# Arduino_extension_connectors.net
KiCad netlist of a schematic drawn in Altium Designer
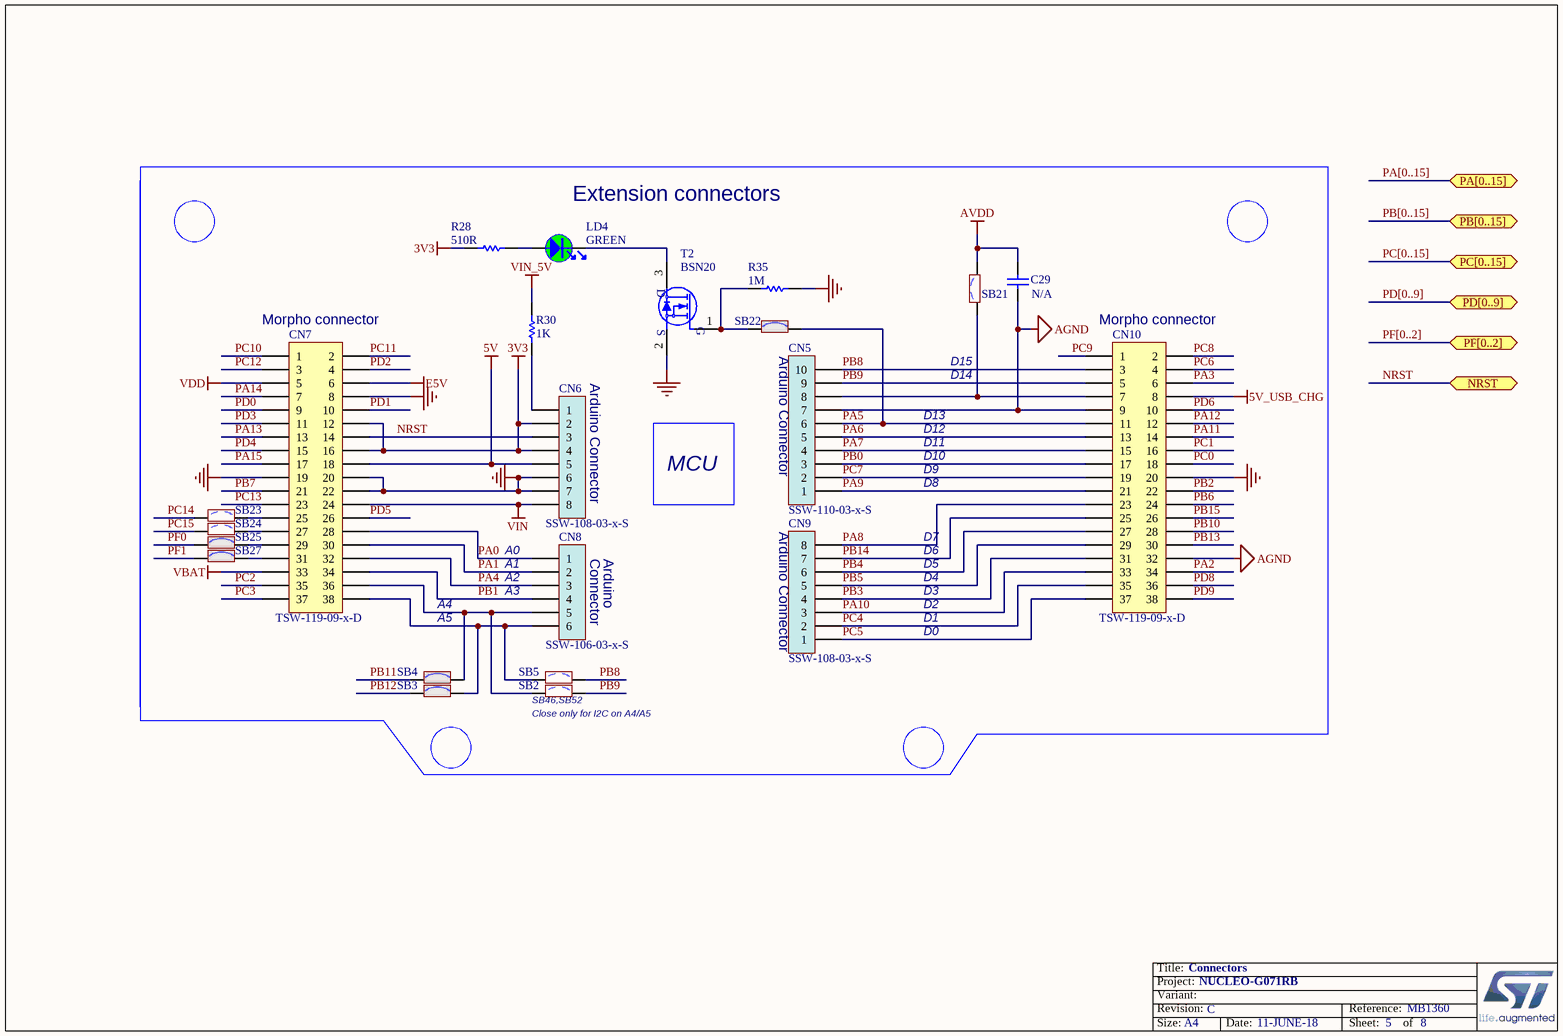
[diagram p0: Arduino_extension_connectors.SchDoc]

(export (version "E")
  (design (tool "Eeschema 10.0.6"))
  (components
    (comp (ref "C29")
      (value "N/A")
      (footprint "C0603")
      (description "Capacitor, MLCC, 100nF, 16V, X7R, 10%, 0603, T=0,8mm")
      (fields
        (field (name "INTERNAL_PART_NUMBER") "MCD-00211")
        (field (name "MANUFACTURER_PART_NUMBER") "CC0603KRX7R7BB104")
        (field (name "PROVIDED_BY") "Subcon")
      )
      (libsource (lib "MCD_PARTS_database") (part "Capacitor"))
    )
    (comp (ref "CN5")
      (value "Socket 10x1")
      (footprint "CON_SAMTEC_SSW-110-03-X-S")
      (description "Socket, 10x1, 2.54mm, VR, TH, Height 8.51mm/10mm")
      (fields
        (field (name "INTERNAL_PART_NUMBER") "MCD-00262")
        (field (name "MANUFACTURER_PART_NUMBER") "SSW-110-03-x-S")
        (field (name "MANUFACTURER") "SAMTEC")
        (field (name "PROVIDED_BY") "Subcon")
      )
      (libsource (lib "MCD_PARTS_database") (part "Socket 10x1"))
    )
    (comp (ref "CN6")
      (value "Socket 8x1")
      (footprint "CON_SAMTEC_SSW-108-03-X-S")
      (description "Socket, 8x1, 2.54mm, VR, TH, Height 8.51mm/10mm")
      (fields
        (field (name "INTERNAL_PART_NUMBER") "MCD-00261")
        (field (name "MANUFACTURER_PART_NUMBER") "SSW-108-03-x-S")
        (field (name "MANUFACTURER") "SAMTEC")
        (field (name "PROVIDED_BY") "Subcon")
      )
      (libsource (lib "") (part "Socket 8x1_1"))
    )
    (comp (ref "CN7")
      (value "Header 19x2")
      (footprint "CON_SAMTEC_TSW-119-09-X-D")
      (description "Header, 19x2, 2,54mm, VR, TH, Height 5.84mm/10.16mm")
      (fields
        (field (name "INTERNAL_PART_NUMBER") "MCD-00213")
        (field (name "MANUFACTURER_PART_NUMBER") "TSW-119-09-x-D")
        (field (name "MANUFACTURER") "SAMTEC")
        (field (name "PROVIDED_BY") "Subcon")
      )
      (libsource (lib "MCD_PARTS_database") (part "Header 19x2"))
    )
    (comp (ref "CN8")
      (value "Socket 6x1")
      (footprint "CON_SAMTEC_SSW-106-03-X-S")
      (description "Socket, 6x1, 2.54mm, VR, TH, Height 8.51mm/10mm")
      (fields
        (field (name "INTERNAL_PART_NUMBER") "MCD-00260")
        (field (name "MANUFACTURER_PART_NUMBER") "SSW-106-03-x-S")
        (field (name "MANUFACTURER") "SAMTEC")
        (field (name "PROVIDED_BY") "Subcon")
      )
      (libsource (lib "MCD_PARTS_database") (part "Socket 6x1"))
    )
    (comp (ref "CN9")
      (value "Socket 8x1")
      (footprint "CON_SAMTEC_SSW-108-03-X-S")
      (description "Socket, 8x1, 2.54mm, VR, TH, Height 8.51mm/10mm")
      (fields
        (field (name "INTERNAL_PART_NUMBER") "MCD-00261")
        (field (name "MANUFACTURER_PART_NUMBER") "SSW-108-03-x-S")
        (field (name "MANUFACTURER") "SAMTEC")
        (field (name "PROVIDED_BY") "Subcon")
      )
      (libsource (lib "MCD_PARTS_database") (part "Socket 8x1"))
    )
    (comp (ref "CN10")
      (value "Header 19x2")
      (footprint "CON_SAMTEC_TSW-119-09-X-D")
      (description "Header, 19x2, 2,54mm, VR, TH, Height 5.84mm/10.16mm")
      (fields
        (field (name "INTERNAL_PART_NUMBER") "MCD-00213")
        (field (name "MANUFACTURER_PART_NUMBER") "TSW-119-09-x-D")
        (field (name "MANUFACTURER") "SAMTEC")
        (field (name "PROVIDED_BY") "Subcon")
      )
      (libsource (lib "MCD_PARTS_database") (part "Header 19x2"))
    )
    (comp (ref "LD4")
      (value "GREEN")
      (footprint "LED_0603_GREEN")
      (description "LED, Green, 0603")
      (fields
        (field (name "INTERNAL_PART_NUMBER") "MCD-00050")
        (field (name "MANUFACTURER_PART_NUMBER") "19-213SYGC/S530-E2/TR8")
        (field (name "PROVIDED_BY") "Subcon")
      )
      (libsource (lib "MCD_PARTS_database") (part "LED_green"))
    )
    (comp (ref "R28")
      (value "510R")
      (footprint "R0603")
      (description "Resistor,510R,0603,1%,1/10W")
      (fields
        (field (name "INTERNAL_PART_NUMBER") "MCD-00225")
        (field (name "MANUFACTURER_PART_NUMBER") "RC0603FR-07510RL")
        (field (name "PROVIDED_BY") "Subcon")
      )
      (libsource (lib "MCD_PARTS_database") (part "Resistor"))
    )
    (comp (ref "R30")
      (value "1K")
      (footprint "R0603")
      (description "Resistor,1K,0603,1%,1/10W")
      (fields
        (field (name "INTERNAL_PART_NUMBER") "MCD-00070")
        (field (name "MANUFACTURER_PART_NUMBER") "RC0603FR-071KL")
        (field (name "PROVIDED_BY") "Subcon")
      )
      (libsource (lib "MCD_PARTS_database") (part "Resistor"))
    )
    (comp (ref "R35")
      (value "1M")
      (footprint "R0603")
      (description "Resistor,1M,0603,1%,1/10W")
      (fields
        (field (name "INTERNAL_PART_NUMBER") "MCD-00257")
        (field (name "MANUFACTURER_PART_NUMBER") "RC0603FR-071ML")
        (field (name "PROVIDED_BY") "Subcon")
      )
      (libsource (lib "MCD_PARTS_database") (part "Resistor"))
    )
    (comp (ref "SB2")
      (value "SB_OFF")
      (footprint "SOLDER-BRIDGE_R0603-0R")
      (description "Solder Bridge OFF")
      (fields (field (name "INTERNAL_PART_NUMBER") "MCD-00072"))
      (libsource (lib "MCD_PARTS_database") (part "SB_OFF"))
    )
    (comp (ref "SB3")
      (value "SB_ON")
      (footprint "SOLDER-BRIDGE_R0603-0R")
      (description "Solder Bridge ON")
      (fields (field (name "INTERNAL_PART_NUMBER") "MCD-00071") (field (name "PROVIDED_BY") "Subcon"))
      (libsource (lib "MCD_PARTS_database") (part "SB_ON"))
    )
    (comp (ref "SB4")
      (value "SB_ON")
      (footprint "SOLDER-BRIDGE_R0603-0R")
      (description "Solder Bridge ON")
      (fields (field (name "INTERNAL_PART_NUMBER") "MCD-00071") (field (name "PROVIDED_BY") "Subcon"))
      (libsource (lib "MCD_PARTS_database") (part "SB_ON"))
    )
    (comp (ref "SB5")
      (value "SB_OFF")
      (footprint "SOLDER-BRIDGE_R0603-0R")
      (description "Solder Bridge OFF")
      (fields (field (name "INTERNAL_PART_NUMBER") "MCD-00072"))
      (libsource (lib "MCD_PARTS_database") (part "SB_OFF"))
    )
    (comp (ref "SB21")
      (value "SB_OFF")
      (footprint "SOLDER-BRIDGE_R0603-0R")
      (description "Solder Bridge OFF")
      (fields (field (name "INTERNAL_PART_NUMBER") "MCD-00072"))
      (libsource (lib "") (part "SB_OFF_1"))
    )
    (comp (ref "SB22")
      (value "SB_ON")
      (footprint "SOLDER-BRIDGE_R0603-0R")
      (description "Solder Bridge ON")
      (fields (field (name "INTERNAL_PART_NUMBER") "MCD-00071") (field (name "PROVIDED_BY") "Subcon"))
      (libsource (lib "MCD_PARTS_database") (part "SB_ON"))
    )
    (comp (ref "SB23")
      (value "SB_OFF")
      (footprint "SOLDER-BRIDGE_R0603-0R")
      (description "Solder Bridge OFF")
      (fields (field (name "INTERNAL_PART_NUMBER") "MCD-00072"))
      (libsource (lib "MCD_PARTS_database") (part "SB_OFF"))
    )
    (comp (ref "SB24")
      (value "SB_OFF")
      (footprint "SOLDER-BRIDGE_R0603-0R")
      (description "Solder Bridge OFF")
      (fields (field (name "INTERNAL_PART_NUMBER") "MCD-00072"))
      (libsource (lib "MCD_PARTS_database") (part "SB_OFF"))
    )
    (comp (ref "SB25")
      (value "SB_ON")
      (footprint "SOLDER-BRIDGE_R0603-0R")
      (description "Solder Bridge ON")
      (fields (field (name "INTERNAL_PART_NUMBER") "MCD-00071") (field (name "PROVIDED_BY") "Subcon"))
      (libsource (lib "MCD_PARTS_database") (part "SB_ON"))
    )
    (comp (ref "SB27")
      (value "SB_ON")
      (footprint "SOLDER-BRIDGE_R0603-0R")
      (description "Solder Bridge ON")
      (fields (field (name "INTERNAL_PART_NUMBER") "MCD-00071") (field (name "PROVIDED_BY") "Subcon"))
      (libsource (lib "MCD_PARTS_database") (part "SB_ON"))
    )
    (comp (ref "T2")
      (value "BSN20")
      (footprint "MOS_SOT23")
      (description "N-channel enhancement mode field-effect transistor")
      (fields
        (field (name "INTERNAL_PART_NUMBER") "MCD-00151")
        (field (name "MANUFACTURER") "NXP")
        (field (name "PROVIDED_BY") "Subcon")
      )
      (libsource (lib "MCD_PARTS_database") (part "BSN20"))
    )
  )
  (nets
    (net (code "3") (name "/NRST") (class "Default")
      (node (ref "CN6") (pin "3") (pinfunction "3_3") (pintype "passive"))
      (node (ref "CN7") (pin "14") (pinfunction "14_14") (pintype "passive"))
    )
    (net (code "4") (name "/PA0") (class "Default")
      (node (ref "CN7") (pin "28") (pinfunction "28_28") (pintype "passive"))
      (node (ref "CN8") (pin "1") (pinfunction "1_1") (pintype "passive"))
    )
    (net (code "5") (name "/PA1") (class "Default")
      (node (ref "CN7") (pin "30") (pinfunction "30_30") (pintype "passive"))
      (node (ref "CN8") (pin "2") (pinfunction "2_2") (pintype "passive"))
    )
    (net (code "6") (name "/PA2") (class "Default")
      (node (ref "CN10") (pin "34") (pinfunction "34_34") (pintype "passive"))
    )
    (net (code "7") (name "/PA3") (class "Default")
      (node (ref "CN10") (pin "6") (pinfunction "6_6") (pintype "passive"))
    )
    (net (code "8") (name "/PA4") (class "Default")
      (node (ref "CN7") (pin "32") (pinfunction "32_32") (pintype "passive"))
      (node (ref "CN8") (pin "3") (pinfunction "3_3") (pintype "passive"))
    )
    (net (code "9") (name "/PA5") (class "Default")
      (node (ref "CN10") (pin "11") (pinfunction "11_11") (pintype "passive"))
      (node (ref "CN5") (pin "6") (pinfunction "6_6") (pintype "passive"))
      (node (ref "SB22") (pin "2") (pinfunction "2_2") (pintype "passive"))
    )
    (net (code "10") (name "/PA6") (class "Default")
      (node (ref "CN10") (pin "13") (pinfunction "13_13") (pintype "passive"))
      (node (ref "CN5") (pin "5") (pinfunction "5_5") (pintype "passive"))
    )
    (net (code "11") (name "/PA7") (class "Default")
      (node (ref "CN10") (pin "15") (pinfunction "15_15") (pintype "passive"))
      (node (ref "CN5") (pin "4") (pinfunction "4_4") (pintype "passive"))
    )
    (net (code "12") (name "/PA8") (class "Default")
      (node (ref "CN10") (pin "23") (pinfunction "23_23") (pintype "passive"))
      (node (ref "CN9") (pin "8") (pinfunction "8_8") (pintype "passive"))
    )
    (net (code "13") (name "/PA9") (class "Default")
      (node (ref "CN10") (pin "21") (pinfunction "21_21") (pintype "passive"))
      (node (ref "CN5") (pin "1") (pinfunction "1_1") (pintype "passive"))
    )
    (net (code "14") (name "/PA10") (class "Default")
      (node (ref "CN10") (pin "33") (pinfunction "33_33") (pintype "passive"))
      (node (ref "CN9") (pin "3") (pinfunction "3_3") (pintype "passive"))
    )
    (net (code "15") (name "/PA11") (class "Default")
      (node (ref "CN10") (pin "14") (pinfunction "14_14") (pintype "passive"))
    )
    (net (code "16") (name "/PA12") (class "Default")
      (node (ref "CN10") (pin "12") (pinfunction "12_12") (pintype "passive"))
    )
    (net (code "17") (name "/PA13") (class "Default")
      (node (ref "CN7") (pin "13") (pinfunction "13_13") (pintype "passive"))
    )
    (net (code "18") (name "/PA14") (class "Default")
      (node (ref "CN7") (pin "7") (pinfunction "7_7") (pintype "passive"))
    )
    (net (code "19") (name "/PA15") (class "Default")
      (node (ref "CN7") (pin "17") (pinfunction "17_17") (pintype "passive"))
    )
    (net (code "21") (name "/PB0") (class "Default")
      (node (ref "CN10") (pin "17") (pinfunction "17_17") (pintype "passive"))
      (node (ref "CN5") (pin "3") (pinfunction "3_3") (pintype "passive"))
    )
    (net (code "22") (name "/PB1") (class "Default")
      (node (ref "CN7") (pin "34") (pinfunction "34_34") (pintype "passive"))
      (node (ref "CN8") (pin "4") (pinfunction "4_4") (pintype "passive"))
    )
    (net (code "23") (name "/PB2") (class "Default")
      (node (ref "CN10") (pin "22") (pinfunction "22_22") (pintype "passive"))
    )
    (net (code "24") (name "/PB3") (class "Default")
      (node (ref "CN10") (pin "31") (pinfunction "31_31") (pintype "passive"))
      (node (ref "CN9") (pin "4") (pinfunction "4_4") (pintype "passive"))
    )
    (net (code "25") (name "/PB4") (class "Default")
      (node (ref "CN10") (pin "27") (pinfunction "27_27") (pintype "passive"))
      (node (ref "CN9") (pin "6") (pinfunction "6_6") (pintype "passive"))
    )
    (net (code "26") (name "/PB5") (class "Default")
      (node (ref "CN10") (pin "29") (pinfunction "29_29") (pintype "passive"))
      (node (ref "CN9") (pin "5") (pinfunction "5_5") (pintype "passive"))
    )
    (net (code "27") (name "/PB6") (class "Default")
      (node (ref "CN10") (pin "24") (pinfunction "24_24") (pintype "passive"))
    )
    (net (code "28") (name "/PB7") (class "Default")
      (node (ref "CN7") (pin "21") (pinfunction "21_21") (pintype "passive"))
    )
    (net (code "29") (name "/PB8") (class "Default")
      (node (ref "CN10") (pin "3") (pinfunction "3_3") (pintype "passive"))
      (node (ref "CN5") (pin "10") (pinfunction "10_10") (pintype "passive"))
      (node (ref "SB5") (pin "2") (pinfunction "2_2") (pintype "passive"))
    )
    (net (code "30") (name "/PB9") (class "Default")
      (node (ref "CN10") (pin "5") (pinfunction "5_5") (pintype "passive"))
      (node (ref "CN5") (pin "9") (pinfunction "9_9") (pintype "passive"))
      (node (ref "SB2") (pin "2") (pinfunction "2_2") (pintype "passive"))
    )
    (net (code "31") (name "/PB10") (class "Default")
      (node (ref "CN10") (pin "28") (pinfunction "28_28") (pintype "passive"))
    )
    (net (code "32") (name "/PB11") (class "Default")
      (node (ref "SB4") (pin "1") (pinfunction "1_1") (pintype "passive"))
    )
    (net (code "33") (name "/PB12") (class "Default")
      (node (ref "SB3") (pin "1") (pinfunction "1_1") (pintype "passive"))
    )
    (net (code "34") (name "/PB13") (class "Default")
      (node (ref "CN10") (pin "30") (pinfunction "30_30") (pintype "passive"))
    )
    (net (code "35") (name "/PB14") (class "Default")
      (node (ref "CN10") (pin "25") (pinfunction "25_25") (pintype "passive"))
      (node (ref "CN9") (pin "7") (pinfunction "7_7") (pintype "passive"))
    )
    (net (code "36") (name "/PB15") (class "Default")
      (node (ref "CN10") (pin "26") (pinfunction "26_26") (pintype "passive"))
    )
    (net (code "38") (name "/PC0") (class "Default")
      (node (ref "CN10") (pin "18") (pinfunction "18_18") (pintype "passive"))
    )
    (net (code "39") (name "/PC1") (class "Default")
      (node (ref "CN10") (pin "16") (pinfunction "16_16") (pintype "passive"))
    )
    (net (code "40") (name "/PC2") (class "Default")
      (node (ref "CN7") (pin "35") (pinfunction "35_35") (pintype "passive"))
    )
    (net (code "41") (name "/PC3") (class "Default")
      (node (ref "CN7") (pin "37") (pinfunction "37_37") (pintype "passive"))
    )
    (net (code "42") (name "/PC4") (class "Default")
      (node (ref "CN10") (pin "35") (pinfunction "35_35") (pintype "passive"))
      (node (ref "CN9") (pin "2") (pinfunction "2_2") (pintype "passive"))
    )
    (net (code "43") (name "/PC5") (class "Default")
      (node (ref "CN10") (pin "37") (pinfunction "37_37") (pintype "passive"))
      (node (ref "CN9") (pin "1") (pinfunction "1_1") (pintype "passive"))
    )
    (net (code "44") (name "/PC6") (class "Default")
      (node (ref "CN10") (pin "4") (pinfunction "4_4") (pintype "passive"))
    )
    (net (code "45") (name "/PC7") (class "Default")
      (node (ref "CN10") (pin "19") (pinfunction "19_19") (pintype "passive"))
      (node (ref "CN5") (pin "2") (pinfunction "2_2") (pintype "passive"))
    )
    (net (code "46") (name "/PC8") (class "Default")
      (node (ref "CN10") (pin "2") (pinfunction "2_2") (pintype "passive"))
    )
    (net (code "47") (name "/PC9") (class "Default")
      (node (ref "CN10") (pin "1") (pinfunction "1_1") (pintype "passive"))
    )
    (net (code "48") (name "/PC10") (class "Default")
      (node (ref "CN7") (pin "1") (pinfunction "1_1") (pintype "passive"))
    )
    (net (code "49") (name "/PC11") (class "Default")
      (node (ref "CN7") (pin "2") (pinfunction "2_2") (pintype "passive"))
    )
    (net (code "50") (name "/PC12") (class "Default")
      (node (ref "CN7") (pin "3") (pinfunction "3_3") (pintype "passive"))
    )
    (net (code "51") (name "/PC13") (class "Default")
      (node (ref "CN7") (pin "23") (pinfunction "23_23") (pintype "passive"))
    )
    (net (code "52") (name "/PC14") (class "Default")
      (node (ref "SB23") (pin "1") (pinfunction "1_1") (pintype "passive"))
    )
    (net (code "53") (name "/PC15") (class "Default")
      (node (ref "SB24") (pin "1") (pinfunction "1_1") (pintype "passive"))
    )
    (net (code "55") (name "/PD0") (class "Default")
      (node (ref "CN7") (pin "9") (pinfunction "9_9") (pintype "passive"))
    )
    (net (code "56") (name "/PD1") (class "Default")
      (node (ref "CN7") (pin "10") (pinfunction "10_10") (pintype "passive"))
    )
    (net (code "57") (name "/PD2") (class "Default")
      (node (ref "CN7") (pin "4") (pinfunction "4_4") (pintype "passive"))
    )
    (net (code "58") (name "/PD3") (class "Default")
      (node (ref "CN7") (pin "11") (pinfunction "11_11") (pintype "passive"))
    )
    (net (code "59") (name "/PD4") (class "Default")
      (node (ref "CN7") (pin "15") (pinfunction "15_15") (pintype "passive"))
    )
    (net (code "60") (name "/PD5") (class "Default")
      (node (ref "CN7") (pin "26") (pinfunction "26_26") (pintype "passive"))
    )
    (net (code "61") (name "/PD6") (class "Default")
      (node (ref "CN10") (pin "10") (pinfunction "10_10") (pintype "passive"))
    )
    (net (code "62") (name "/PD8") (class "Default")
      (node (ref "CN10") (pin "36") (pinfunction "36_36") (pintype "passive"))
    )
    (net (code "63") (name "/PD9") (class "Default")
      (node (ref "CN10") (pin "38") (pinfunction "38_38") (pintype "passive"))
    )
    (net (code "65") (name "/PF0") (class "Default")
      (node (ref "SB25") (pin "1") (pinfunction "1_1") (pintype "passive"))
    )
    (net (code "66") (name "/PF1") (class "Default")
      (node (ref "SB27") (pin "1") (pinfunction "1_1") (pintype "passive"))
    )
    (net (code "68") (name "3V3") (class "Default")
      (node (ref "CN6") (pin "2") (pinfunction "2_2") (pintype "passive"))
      (node (ref "CN6") (pin "4") (pinfunction "4_4") (pintype "passive"))
      (node (ref "CN7") (pin "12") (pinfunction "12_12") (pintype "passive"))
      (node (ref "CN7") (pin "16") (pinfunction "16_16") (pintype "passive"))
      (node (ref "R28") (pin "2") (pinfunction "2_2") (pintype "passive"))
    )
    (net (code "69") (name "5V") (class "Default")
      (node (ref "CN6") (pin "5") (pinfunction "5_5") (pintype "passive"))
      (node (ref "CN7") (pin "18") (pinfunction "18_18") (pintype "passive"))
    )
    (net (code "70") (name "5V_USB_CHG") (class "Default")
      (node (ref "CN10") (pin "8") (pinfunction "8_8") (pintype "passive"))
    )
    (net (code "71") (name "AGND") (class "Default")
      (node (ref "C29") (pin "1") (pinfunction "1_1") (pintype "passive"))
      (node (ref "CN10") (pin "32") (pinfunction "32_32") (pintype "passive"))
      (node (ref "CN10") (pin "9") (pinfunction "9_9") (pintype "passive"))
      (node (ref "CN5") (pin "7") (pinfunction "7_7") (pintype "passive"))
    )
    (net (code "72") (name "AVDD") (class "Default")
      (node (ref "C29") (pin "2") (pinfunction "2_2") (pintype "passive"))
      (node (ref "SB21") (pin "2") (pinfunction "2_2") (pintype "passive"))
    )
    (net (code "73") (name "E5V") (class "Default")
      (node (ref "CN7") (pin "6") (pinfunction "6_6") (pintype "passive"))
    )
    (net (code "74") (name "GND") (class "Default")
      (node (ref "CN10") (pin "20") (pinfunction "20_20") (pintype "passive"))
      (node (ref "CN6") (pin "6") (pinfunction "6_6") (pintype "passive"))
      (node (ref "CN6") (pin "7") (pinfunction "7_7") (pintype "passive"))
      (node (ref "CN7") (pin "19") (pinfunction "19_19") (pintype "passive"))
      (node (ref "CN7") (pin "20") (pinfunction "20_20") (pintype "passive"))
      (node (ref "CN7") (pin "22") (pinfunction "22_22") (pintype "passive"))
      (node (ref "CN7") (pin "8") (pinfunction "8_8") (pintype "passive"))
      (node (ref "R35") (pin "2") (pinfunction "2_2") (pintype "passive"))
      (node (ref "T2") (pin "2") (pinfunction "S_2") (pintype "passive"))
    )
    (net (code "75") (name "Net-(CN6-Pad1)") (class "Default")
      (node (ref "CN6") (pin "1") (pinfunction "1_1") (pintype "passive"))
      (node (ref "R30") (pin "2") (pinfunction "2_2") (pintype "passive"))
    )
    (net (code "76") (name "Net-(CN7-Pad25)") (class "Default")
      (node (ref "CN7") (pin "25") (pinfunction "25_25") (pintype "passive"))
      (node (ref "SB23") (pin "2") (pinfunction "2_2") (pintype "passive"))
    )
    (net (code "77") (name "Net-(CN7-Pad27)") (class "Default")
      (node (ref "CN7") (pin "27") (pinfunction "27_27") (pintype "passive"))
      (node (ref "SB24") (pin "2") (pinfunction "2_2") (pintype "passive"))
    )
    (net (code "78") (name "Net-(CN7-Pad29)") (class "Default")
      (node (ref "CN7") (pin "29") (pinfunction "29_29") (pintype "passive"))
      (node (ref "SB25") (pin "2") (pinfunction "2_2") (pintype "passive"))
    )
    (net (code "79") (name "Net-(CN7-Pad31)") (class "Default")
      (node (ref "CN7") (pin "31") (pinfunction "31_31") (pintype "passive"))
      (node (ref "SB27") (pin "2") (pinfunction "2_2") (pintype "passive"))
    )
    (net (code "80") (name "Net-(CN7-Pad36)") (class "Default")
      (node (ref "CN7") (pin "36") (pinfunction "36_36") (pintype "passive"))
      (node (ref "CN8") (pin "5") (pinfunction "5_5") (pintype "passive"))
      (node (ref "SB2") (pin "1") (pinfunction "1_1") (pintype "passive"))
      (node (ref "SB4") (pin "2") (pinfunction "2_2") (pintype "passive"))
    )
    (net (code "81") (name "Net-(CN7-Pad38)") (class "Default")
      (node (ref "CN7") (pin "38") (pinfunction "38_38") (pintype "passive"))
      (node (ref "CN8") (pin "6") (pinfunction "6_6") (pintype "passive"))
      (node (ref "SB3") (pin "2") (pinfunction "2_2") (pintype "passive"))
      (node (ref "SB5") (pin "1") (pinfunction "1_1") (pintype "passive"))
    )
    (net (code "82") (name "Net-(CN10-Pad7)") (class "Default")
      (node (ref "CN10") (pin "7") (pinfunction "7_7") (pintype "passive"))
      (node (ref "CN5") (pin "8") (pinfunction "8_8") (pintype "passive"))
      (node (ref "SB21") (pin "1") (pinfunction "1_1") (pintype "passive"))
    )
    (net (code "83") (name "Net-(LD4-Pad1)") (class "Default")
      (node (ref "LD4") (pin "1") (pintype "passive"))
      (node (ref "R28") (pin "1") (pinfunction "1_1") (pintype "passive"))
    )
    (net (code "84") (name "Net-(T2-D)") (class "Default")
      (node (ref "LD4") (pin "2") (pintype "passive"))
      (node (ref "T2") (pin "3") (pinfunction "D_3") (pintype "passive"))
    )
    (net (code "85") (name "Net-(T2-G)") (class "Default")
      (node (ref "R35") (pin "1") (pinfunction "1_1") (pintype "passive"))
      (node (ref "SB22") (pin "1") (pinfunction "1_1") (pintype "passive"))
      (node (ref "T2") (pin "1") (pinfunction "G_1") (pintype "passive"))
    )
    (net (code "86") (name "VBAT") (class "Default")
      (node (ref "CN7") (pin "33") (pinfunction "33_33") (pintype "passive"))
    )
    (net (code "87") (name "VDD") (class "Default")
      (node (ref "CN7") (pin "5") (pinfunction "5_5") (pintype "passive"))
    )
    (net (code "88") (name "VIN") (class "Default")
      (node (ref "CN6") (pin "8") (pinfunction "8_8") (pintype "passive"))
      (node (ref "CN7") (pin "24") (pinfunction "24_24") (pintype "passive"))
    )
    (net (code "89") (name "VIN_5V") (class "Default")
      (node (ref "R30") (pin "1") (pinfunction "1_1") (pintype "passive"))
    )
  )
)
